# Genesis.net
KiCad netlist of a schematic drawn in EAGLE
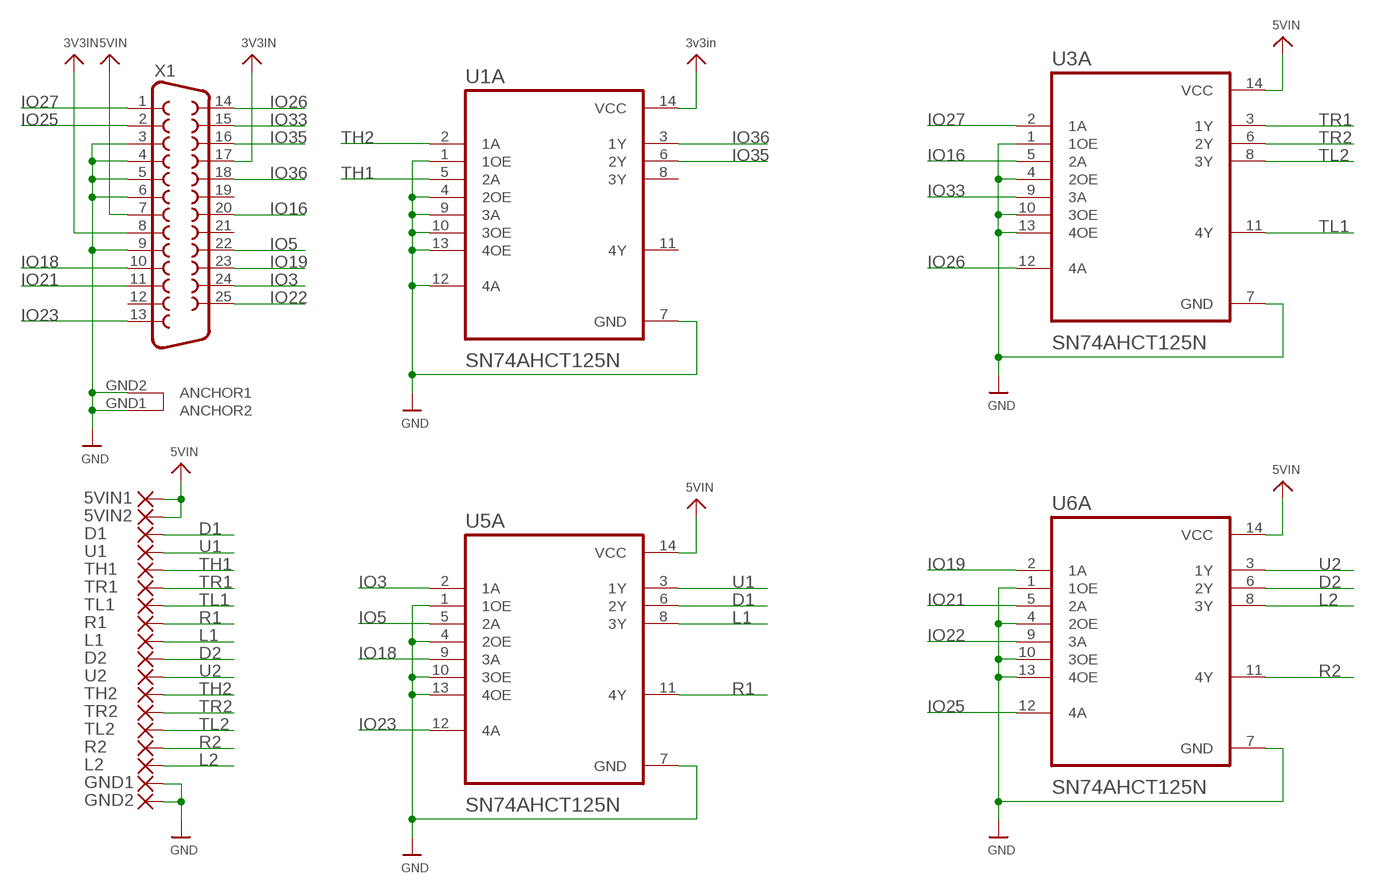
[diagram p0: schematic, sheet 1]

(export (version "E")
  (design (tool "Eeschema 10.0.6"))
  (components
    (comp (ref "5VIN1")
      (value "SMD5")
      (footprint "eagle-import:SMD2,54-5,08")
      (libsource (lib "eagle-import") (part "SMD5"))
    )
    (comp (ref "5VIN2")
      (value "SMD5")
      (footprint "eagle-import:SMD2,54-5,08")
      (libsource (lib "eagle-import") (part "SMD5"))
    )
    (comp (ref "D1")
      (value "SMD5")
      (footprint "eagle-import:SMD2,54-5,08")
      (libsource (lib "eagle-import") (part "SMD5"))
    )
    (comp (ref "D2")
      (value "SMD5")
      (footprint "eagle-import:SMD2,54-5,08")
      (libsource (lib "eagle-import") (part "SMD5"))
    )
    (comp (ref "GND1")
      (value "SMD5")
      (footprint "eagle-import:SMD2,54-5,08")
      (libsource (lib "eagle-import") (part "SMD5"))
    )
    (comp (ref "GND2")
      (value "SMD5")
      (footprint "eagle-import:SMD2,54-5,08")
      (libsource (lib "eagle-import") (part "SMD5"))
    )
    (comp (ref "L1")
      (value "SMD5")
      (footprint "eagle-import:SMD2,54-5,08")
      (libsource (lib "eagle-import") (part "SMD5"))
    )
    (comp (ref "L2")
      (value "SMD5")
      (footprint "eagle-import:SMD2,54-5,08")
      (libsource (lib "eagle-import") (part "SMD5"))
    )
    (comp (ref "R1")
      (value "SMD5")
      (footprint "eagle-import:SMD2,54-5,08")
      (libsource (lib "eagle-import") (part "SMD5"))
    )
    (comp (ref "R2")
      (value "SMD5")
      (footprint "eagle-import:SMD2,54-5,08")
      (libsource (lib "eagle-import") (part "SMD5"))
    )
    (comp (ref "TH1")
      (value "SMD5")
      (footprint "eagle-import:SMD2,54-5,08")
      (libsource (lib "eagle-import") (part "SMD5"))
    )
    (comp (ref "TH2")
      (value "SMD5")
      (footprint "eagle-import:SMD2,54-5,08")
      (libsource (lib "eagle-import") (part "SMD5"))
    )
    (comp (ref "TL1")
      (value "SMD5")
      (footprint "eagle-import:SMD2,54-5,08")
      (libsource (lib "eagle-import") (part "SMD5"))
    )
    (comp (ref "TL2")
      (value "SMD5")
      (footprint "eagle-import:SMD2,54-5,08")
      (libsource (lib "eagle-import") (part "SMD5"))
    )
    (comp (ref "TR1")
      (value "SMD5")
      (footprint "eagle-import:SMD2,54-5,08")
      (libsource (lib "eagle-import") (part "SMD5"))
    )
    (comp (ref "TR2")
      (value "SMD5")
      (footprint "eagle-import:SMD2,54-5,08")
      (libsource (lib "eagle-import") (part "SMD5"))
    )
    (comp (ref "U1")
      (value "SMD5")
      (footprint "eagle-import:SMD2,54-5,08")
      (libsource (lib "eagle-import") (part "SMD5"))
    )
    (comp (ref "U1A")
      (value "SN74AHCT125N")
      (footprint "eagle-import:DIP794W45P254L1969H508Q14")
      (fields (field (name "MF") "Texas Instruments"))
      (libsource (lib "eagle-import") (part "SN74AHCT125N"))
    )
    (comp (ref "U2")
      (value "SMD5")
      (footprint "eagle-import:SMD2,54-5,08")
      (libsource (lib "eagle-import") (part "SMD5"))
    )
    (comp (ref "U3A")
      (value "SN74AHCT125N")
      (footprint "eagle-import:DIP794W45P254L1969H508Q14")
      (fields (field (name "MF") "Texas Instruments"))
      (libsource (lib "eagle-import") (part "SN74AHCT125N"))
    )
    (comp (ref "U5A")
      (value "SN74AHCT125N")
      (footprint "eagle-import:DIP794W45P254L1969H508Q14")
      (fields (field (name "MF") "Texas Instruments"))
      (libsource (lib "eagle-import") (part "SN74AHCT125N"))
    )
    (comp (ref "U6A")
      (value "SN74AHCT125N")
      (footprint "eagle-import:DIP794W45P254L1969H508Q14")
      (fields (field (name "MF") "Texas Instruments"))
      (libsource (lib "eagle-import") (part "SN74AHCT125N"))
    )
    (comp (ref "X1")
      (value "DB25_FEMALEHP")
      (footprint "eagle-import:F25HP")
      (libsource (lib "eagle-import") (part "DB25_FEMALEHP"))
    )
  )
  (nets
    (net (code "1") (name "/D1") (class "Default")
      (node (ref "D1") (pin "1") (pinfunction "P_1") (pintype "passive"))
      (node (ref "U5A") (pin "6") (pinfunction "2Y_6") (pintype "output"))
    )
    (net (code "2") (name "/D2") (class "Default")
      (node (ref "D2") (pin "1") (pinfunction "P_1") (pintype "passive"))
      (node (ref "U6A") (pin "6") (pinfunction "2Y_6") (pintype "output"))
    )
    (net (code "3") (name "/IO3") (class "Default")
      (node (ref "U5A") (pin "2") (pinfunction "1A_2") (pintype "input"))
      (node (ref "X1") (pin "24") (pinfunction "24_24") (pintype "passive"))
    )
    (net (code "4") (name "/IO5") (class "Default")
      (node (ref "U5A") (pin "5") (pinfunction "2A_5") (pintype "input"))
      (node (ref "X1") (pin "22") (pinfunction "22_22") (pintype "passive"))
    )
    (net (code "5") (name "/IO16") (class "Default")
      (node (ref "U3A") (pin "5") (pinfunction "2A_5") (pintype "input"))
      (node (ref "X1") (pin "20") (pinfunction "20_20") (pintype "passive"))
    )
    (net (code "6") (name "/IO18") (class "Default")
      (node (ref "U5A") (pin "9") (pinfunction "3A_9") (pintype "input"))
      (node (ref "X1") (pin "10") (pinfunction "10_10") (pintype "passive"))
    )
    (net (code "7") (name "/IO19") (class "Default")
      (node (ref "U6A") (pin "2") (pinfunction "1A_2") (pintype "input"))
      (node (ref "X1") (pin "23") (pinfunction "23_23") (pintype "passive"))
    )
    (net (code "8") (name "/IO21") (class "Default")
      (node (ref "U6A") (pin "5") (pinfunction "2A_5") (pintype "input"))
      (node (ref "X1") (pin "11") (pinfunction "11_11") (pintype "passive"))
    )
    (net (code "9") (name "/IO22") (class "Default")
      (node (ref "U6A") (pin "9") (pinfunction "3A_9") (pintype "input"))
      (node (ref "X1") (pin "25") (pinfunction "25_25") (pintype "passive"))
    )
    (net (code "10") (name "/IO23") (class "Default")
      (node (ref "U5A") (pin "12") (pinfunction "4A_12") (pintype "bidirectional"))
      (node (ref "X1") (pin "13") (pinfunction "13_13") (pintype "passive"))
    )
    (net (code "11") (name "/IO25") (class "Default")
      (node (ref "U6A") (pin "12") (pinfunction "4A_12") (pintype "bidirectional"))
      (node (ref "X1") (pin "2") (pinfunction "2_2") (pintype "passive"))
    )
    (net (code "12") (name "/IO26") (class "Default")
      (node (ref "U3A") (pin "12") (pinfunction "4A_12") (pintype "bidirectional"))
      (node (ref "X1") (pin "14") (pinfunction "14_14") (pintype "passive"))
    )
    (net (code "13") (name "/IO27") (class "Default")
      (node (ref "U3A") (pin "2") (pinfunction "1A_2") (pintype "input"))
      (node (ref "X1") (pin "1") (pinfunction "1_1") (pintype "passive"))
    )
    (net (code "14") (name "/IO33") (class "Default")
      (node (ref "U3A") (pin "9") (pinfunction "3A_9") (pintype "input"))
      (node (ref "X1") (pin "15") (pinfunction "15_15") (pintype "passive"))
    )
    (net (code "15") (name "/IO35") (class "Default")
      (node (ref "U1A") (pin "6") (pinfunction "2Y_6") (pintype "output"))
      (node (ref "X1") (pin "16") (pinfunction "16_16") (pintype "passive"))
    )
    (net (code "16") (name "/IO36") (class "Default")
      (node (ref "U1A") (pin "3") (pinfunction "1Y_3") (pintype "output"))
      (node (ref "X1") (pin "18") (pinfunction "18_18") (pintype "passive"))
    )
    (net (code "17") (name "/L1") (class "Default")
      (node (ref "L1") (pin "1") (pinfunction "P_1") (pintype "passive"))
      (node (ref "U5A") (pin "8") (pinfunction "3Y_8") (pintype "output"))
    )
    (net (code "18") (name "/L2") (class "Default")
      (node (ref "L2") (pin "1") (pinfunction "P_1") (pintype "passive"))
      (node (ref "U6A") (pin "8") (pinfunction "3Y_8") (pintype "output"))
    )
    (net (code "19") (name "/R1") (class "Default")
      (node (ref "R1") (pin "1") (pinfunction "P_1") (pintype "passive"))
      (node (ref "U5A") (pin "11") (pinfunction "4Y_11") (pintype "output"))
    )
    (net (code "20") (name "/R2") (class "Default")
      (node (ref "R2") (pin "1") (pinfunction "P_1") (pintype "passive"))
      (node (ref "U6A") (pin "11") (pinfunction "4Y_11") (pintype "output"))
    )
    (net (code "21") (name "/TH1") (class "Default")
      (node (ref "TH1") (pin "1") (pinfunction "P_1") (pintype "passive"))
      (node (ref "U1A") (pin "5") (pinfunction "2A_5") (pintype "input"))
    )
    (net (code "22") (name "/TH2") (class "Default")
      (node (ref "TH2") (pin "1") (pinfunction "P_1") (pintype "passive"))
      (node (ref "U1A") (pin "2") (pinfunction "1A_2") (pintype "input"))
    )
    (net (code "23") (name "/TL1") (class "Default")
      (node (ref "TL1") (pin "1") (pinfunction "P_1") (pintype "passive"))
      (node (ref "U3A") (pin "11") (pinfunction "4Y_11") (pintype "output"))
    )
    (net (code "24") (name "/TL2") (class "Default")
      (node (ref "TL2") (pin "1") (pinfunction "P_1") (pintype "passive"))
      (node (ref "U3A") (pin "8") (pinfunction "3Y_8") (pintype "output"))
    )
    (net (code "25") (name "/TR1") (class "Default")
      (node (ref "TR1") (pin "1") (pinfunction "P_1") (pintype "passive"))
      (node (ref "U3A") (pin "3") (pinfunction "1Y_3") (pintype "output"))
    )
    (net (code "26") (name "/TR2") (class "Default")
      (node (ref "TR2") (pin "1") (pinfunction "P_1") (pintype "passive"))
      (node (ref "U3A") (pin "6") (pinfunction "2Y_6") (pintype "output"))
    )
    (net (code "27") (name "/U1") (class "Default")
      (node (ref "U1") (pin "1") (pinfunction "P_1") (pintype "passive"))
      (node (ref "U5A") (pin "3") (pinfunction "1Y_3") (pintype "output"))
    )
    (net (code "28") (name "/U2") (class "Default")
      (node (ref "U2") (pin "1") (pinfunction "P_1") (pintype "passive"))
      (node (ref "U6A") (pin "3") (pinfunction "1Y_3") (pintype "output"))
    )
    (net (code "29") (name "3V3IN") (class "Default")
      (node (ref "U1A") (pin "14") (pinfunction "VCC_14") (pintype "power_in"))
      (node (ref "X1") (pin "17") (pinfunction "17_17") (pintype "passive"))
      (node (ref "X1") (pin "8") (pinfunction "8_8") (pintype "passive"))
    )
    (net (code "30") (name "5VIN") (class "Default")
      (node (ref "5VIN1") (pin "1") (pinfunction "P_1") (pintype "passive"))
      (node (ref "5VIN2") (pin "1") (pinfunction "P_1") (pintype "passive"))
      (node (ref "U3A") (pin "14") (pinfunction "VCC_14") (pintype "power_in"))
      (node (ref "U5A") (pin "14") (pinfunction "VCC_14") (pintype "power_in"))
      (node (ref "U6A") (pin "14") (pinfunction "VCC_14") (pintype "power_in"))
      (node (ref "X1") (pin "7") (pinfunction "7_7") (pintype "passive"))
    )
    (net (code "31") (name "GND") (class "Default")
      (node (ref "GND1") (pin "1") (pinfunction "P_1") (pintype "passive"))
      (node (ref "GND2") (pin "1") (pinfunction "P_1") (pintype "passive"))
      (node (ref "U1A") (pin "1") (pinfunction "1OE_1") (pintype "input"))
      (node (ref "U1A") (pin "10") (pinfunction "3OE_10") (pintype "input"))
      (node (ref "U1A") (pin "12") (pinfunction "4A_12") (pintype "bidirectional"))
      (node (ref "U1A") (pin "13") (pinfunction "4OE_13") (pintype "input"))
      (node (ref "U1A") (pin "4") (pinfunction "2OE_4") (pintype "input"))
      (node (ref "U1A") (pin "7") (pinfunction "GND_7") (pintype "power_in"))
      (node (ref "U1A") (pin "9") (pinfunction "3A_9") (pintype "input"))
      (node (ref "U3A") (pin "1") (pinfunction "1OE_1") (pintype "input"))
      (node (ref "U3A") (pin "10") (pinfunction "3OE_10") (pintype "input"))
      (node (ref "U3A") (pin "13") (pinfunction "4OE_13") (pintype "input"))
      (node (ref "U3A") (pin "4") (pinfunction "2OE_4") (pintype "input"))
      (node (ref "U3A") (pin "7") (pinfunction "GND_7") (pintype "power_in"))
      (node (ref "U5A") (pin "1") (pinfunction "1OE_1") (pintype "input"))
      (node (ref "U5A") (pin "10") (pinfunction "3OE_10") (pintype "input"))
      (node (ref "U5A") (pin "13") (pinfunction "4OE_13") (pintype "input"))
      (node (ref "U5A") (pin "4") (pinfunction "2OE_4") (pintype "input"))
      (node (ref "U5A") (pin "7") (pinfunction "GND_7") (pintype "power_in"))
      (node (ref "U6A") (pin "1") (pinfunction "1OE_1") (pintype "input"))
      (node (ref "U6A") (pin "10") (pinfunction "3OE_10") (pintype "input"))
      (node (ref "U6A") (pin "13") (pinfunction "4OE_13") (pintype "input"))
      (node (ref "U6A") (pin "4") (pinfunction "2OE_4") (pintype "input"))
      (node (ref "U6A") (pin "7") (pinfunction "GND_7") (pintype "power_in"))
      (node (ref "X1") (pin "3") (pinfunction "3_3") (pintype "passive"))
      (node (ref "X1") (pin "4") (pinfunction "4_4") (pintype "passive"))
      (node (ref "X1") (pin "5") (pinfunction "5_5") (pintype "passive"))
      (node (ref "X1") (pin "6") (pinfunction "6_6") (pintype "passive"))
      (node (ref "X1") (pin "9") (pinfunction "9_9") (pintype "passive"))
      (node (ref "X1") (pin "GND1") (pinfunction "ANCHOR2_GND1") (pintype "bidirectional"))
      (node (ref "X1") (pin "GND2") (pinfunction "ANCHOR1_GND2") (pintype "bidirectional"))
    )
    (net (code "32") (name "unconnected-(U1A-3Y-Pad8)") (class "Default")
      (node (ref "U1A") (pin "8") (pinfunction "3Y_8") (pintype "output"))
    )
    (net (code "33") (name "unconnected-(U1A-4Y-Pad11)") (class "Default")
      (node (ref "U1A") (pin "11") (pinfunction "4Y_11") (pintype "output"))
    )
    (net (code "34") (name "unconnected-(X1-Pad12)") (class "Default")
      (node (ref "X1") (pin "12") (pinfunction "12_12") (pintype "passive"))
    )
    (net (code "35") (name "unconnected-(X1-Pad19)") (class "Default")
      (node (ref "X1") (pin "19") (pinfunction "19_19") (pintype "passive"))
    )
    (net (code "36") (name "unconnected-(X1-Pad21)") (class "Default")
      (node (ref "X1") (pin "21") (pinfunction "21_21") (pintype "passive"))
    )
  )
)
